# Seaquencer.net
KiCad netlist of a schematic drawn in EAGLE
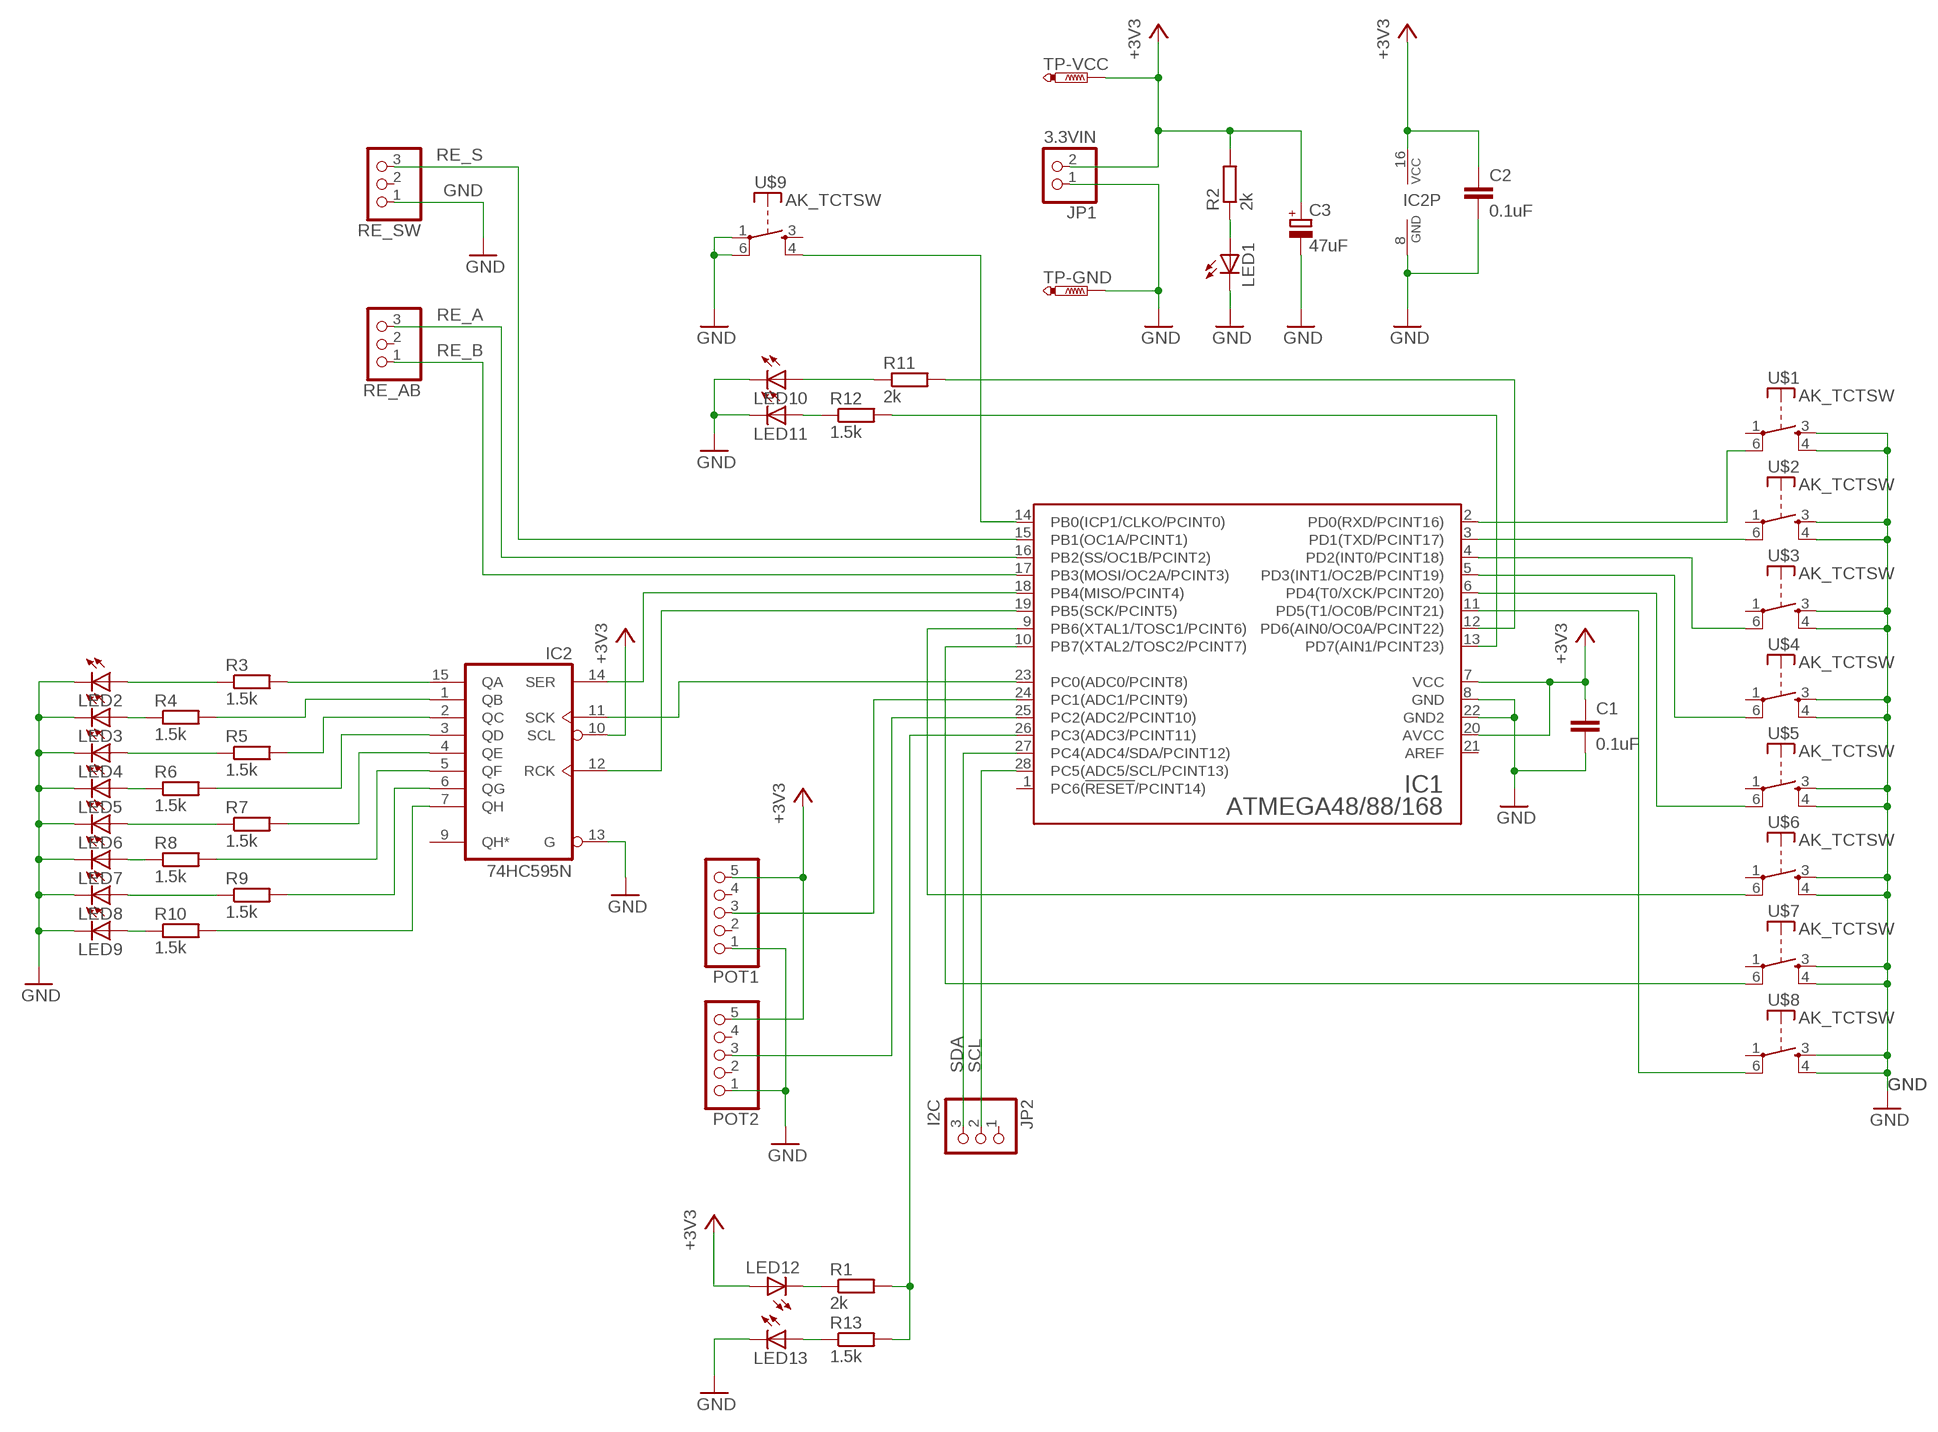
[diagram p0: schematic, sheet 1]

(export (version "E")
  (design (tool "Eeschema 10.0.6"))
  (components
    (comp (ref "C1")
      (value "0.1uF")
      (footprint "eagle-import:C025-024X044")
      (libsource (lib "eagle-import") (part "C-EU025-024X044"))
    )
    (comp (ref "C2")
      (value "0.1uF")
      (footprint "eagle-import:C025-024X044")
      (libsource (lib "eagle-import") (part "C-EU025-024X044"))
    )
    (comp (ref "C3")
      (value "47uF")
      (footprint "eagle-import:E2,5-6")
      (libsource (lib "eagle-import") (part "CPOL-EUE2.5-6"))
    )
    (comp (ref "IC1")
      (value "ATMEGA48/88/168")
      (footprint "eagle-import:DIL28-3")
      (libsource (lib "eagle-import") (part "ATMEGA48/88/168"))
    )
    (comp (ref "IC2")
      (value "74HC595N")
      (footprint "eagle-import:DIL16")
      (libsource (lib "eagle-import") (part "74595NHC"))
    )
    (comp (ref "JP1")
      (value "3.3VIN")
      (footprint "eagle-import:1X02")
      (libsource (lib "eagle-import") (part "PINHD-1X2"))
    )
    (comp (ref "JP2")
      (value "I2C")
      (footprint "eagle-import:1X03")
      (libsource (lib "eagle-import") (part "PINHD-1X3"))
    )
    (comp (ref "LED1")
      (value "LED3MM")
      (footprint "eagle-import:LED3MM")
      (libsource (lib "eagle-import") (part "LED3MM"))
    )
    (comp (ref "LED2")
      (value "LED3MM")
      (footprint "eagle-import:LED3MM")
      (libsource (lib "eagle-import") (part "LED3MM"))
    )
    (comp (ref "LED3")
      (value "LED3MM")
      (footprint "eagle-import:LED3MM")
      (libsource (lib "eagle-import") (part "LED3MM"))
    )
    (comp (ref "LED4")
      (value "LED3MM")
      (footprint "eagle-import:LED3MM")
      (libsource (lib "eagle-import") (part "LED3MM"))
    )
    (comp (ref "LED5")
      (value "LED3MM")
      (footprint "eagle-import:LED3MM")
      (libsource (lib "eagle-import") (part "LED3MM"))
    )
    (comp (ref "LED6")
      (value "LED3MM")
      (footprint "eagle-import:LED3MM")
      (libsource (lib "eagle-import") (part "LED3MM"))
    )
    (comp (ref "LED7")
      (value "LED3MM")
      (footprint "eagle-import:LED3MM")
      (libsource (lib "eagle-import") (part "LED3MM"))
    )
    (comp (ref "LED8")
      (value "LED3MM")
      (footprint "eagle-import:LED3MM")
      (libsource (lib "eagle-import") (part "LED3MM"))
    )
    (comp (ref "LED9")
      (value "LED3MM")
      (footprint "eagle-import:LED3MM")
      (libsource (lib "eagle-import") (part "LED3MM"))
    )
    (comp (ref "LED10")
      (value "LED3MM")
      (footprint "eagle-import:LED3MM")
      (libsource (lib "eagle-import") (part "LED3MM"))
    )
    (comp (ref "LED11")
      (value "LED3MM")
      (footprint "eagle-import:LED3MM")
      (libsource (lib "eagle-import") (part "LED3MM"))
    )
    (comp (ref "LED12")
      (value "LED3MM")
      (footprint "eagle-import:LED3MM")
      (libsource (lib "eagle-import") (part "LED3MM"))
    )
    (comp (ref "LED13")
      (value "LED3MM")
      (footprint "eagle-import:LED3MM")
      (libsource (lib "eagle-import") (part "LED3MM"))
    )
    (comp (ref "POT1")
      (value "PINHD-1X5")
      (footprint "eagle-import:1X05")
      (libsource (lib "eagle-import") (part "PINHD-1X5"))
    )
    (comp (ref "POT2")
      (value "PINHD-1X5")
      (footprint "eagle-import:1X05")
      (libsource (lib "eagle-import") (part "PINHD-1X5"))
    )
    (comp (ref "R1")
      (value "2k")
      (footprint "eagle-import:0207_7")
      (libsource (lib "eagle-import") (part "R-EU_0207/7"))
    )
    (comp (ref "R2")
      (value "2k")
      (footprint "eagle-import:0207_7")
      (libsource (lib "eagle-import") (part "R-EU_0207/7"))
    )
    (comp (ref "R3")
      (value "1.5k")
      (footprint "eagle-import:0207_7")
      (libsource (lib "eagle-import") (part "R-EU_0207/7"))
    )
    (comp (ref "R4")
      (value "1.5k")
      (footprint "eagle-import:0207_7")
      (libsource (lib "eagle-import") (part "R-EU_0207/7"))
    )
    (comp (ref "R5")
      (value "1.5k")
      (footprint "eagle-import:0207_7")
      (libsource (lib "eagle-import") (part "R-EU_0207/7"))
    )
    (comp (ref "R6")
      (value "1.5k")
      (footprint "eagle-import:0207_7")
      (libsource (lib "eagle-import") (part "R-EU_0207/7"))
    )
    (comp (ref "R7")
      (value "1.5k")
      (footprint "eagle-import:0207_7")
      (libsource (lib "eagle-import") (part "R-EU_0207/7"))
    )
    (comp (ref "R8")
      (value "1.5k")
      (footprint "eagle-import:0207_7")
      (libsource (lib "eagle-import") (part "R-EU_0207/7"))
    )
    (comp (ref "R9")
      (value "1.5k")
      (footprint "eagle-import:0207_7")
      (libsource (lib "eagle-import") (part "R-EU_0207/7"))
    )
    (comp (ref "R10")
      (value "1.5k")
      (footprint "eagle-import:0207_7")
      (libsource (lib "eagle-import") (part "R-EU_0207/7"))
    )
    (comp (ref "R11")
      (value "2k")
      (footprint "eagle-import:0207_7")
      (libsource (lib "eagle-import") (part "R-EU_0207/7"))
    )
    (comp (ref "R12")
      (value "1.5k")
      (footprint "eagle-import:0207_7")
      (libsource (lib "eagle-import") (part "R-EU_0207/7"))
    )
    (comp (ref "R13")
      (value "1.5k")
      (footprint "eagle-import:0207_7")
      (libsource (lib "eagle-import") (part "R-EU_0207/7"))
    )
    (comp (ref "RE_AB")
      (value "PINHD-1X3")
      (footprint "eagle-import:1X03")
      (libsource (lib "eagle-import") (part "PINHD-1X3"))
    )
    (comp (ref "RE_SW")
      (value "PINHD-1X3")
      (footprint "eagle-import:1X03")
      (libsource (lib "eagle-import") (part "PINHD-1X3"))
    )
    (comp (ref "TP-GND")
      (value "PTR1PAD1-13")
      (footprint "eagle-import:P1-13")
      (libsource (lib "eagle-import") (part "PTR1PAD1-13"))
    )
    (comp (ref "TP-VCC")
      (value "PTR1PAD1-13")
      (footprint "eagle-import:P1-13")
      (libsource (lib "eagle-import") (part "PTR1PAD1-13"))
    )
    (comp (ref "U$1")
      (value "AK_TCTSW")
      (footprint "eagle-import:TME1")
      (libsource (lib "eagle-import") (part "AK_TCTSW"))
    )
    (comp (ref "U$2")
      (value "AK_TCTSW")
      (footprint "eagle-import:TME1")
      (libsource (lib "eagle-import") (part "AK_TCTSW"))
    )
    (comp (ref "U$3")
      (value "AK_TCTSW")
      (footprint "eagle-import:TME1")
      (libsource (lib "eagle-import") (part "AK_TCTSW"))
    )
    (comp (ref "U$4")
      (value "AK_TCTSW")
      (footprint "eagle-import:TME1")
      (libsource (lib "eagle-import") (part "AK_TCTSW"))
    )
    (comp (ref "U$5")
      (value "AK_TCTSW")
      (footprint "eagle-import:TME1")
      (libsource (lib "eagle-import") (part "AK_TCTSW"))
    )
    (comp (ref "U$6")
      (value "AK_TCTSW")
      (footprint "eagle-import:TME1")
      (libsource (lib "eagle-import") (part "AK_TCTSW"))
    )
    (comp (ref "U$7")
      (value "AK_TCTSW")
      (footprint "eagle-import:TME1")
      (libsource (lib "eagle-import") (part "AK_TCTSW"))
    )
    (comp (ref "U$8")
      (value "AK_TCTSW")
      (footprint "eagle-import:TME1")
      (libsource (lib "eagle-import") (part "AK_TCTSW"))
    )
    (comp (ref "U$9")
      (value "AK_TCTSW")
      (footprint "eagle-import:TME1")
      (libsource (lib "eagle-import") (part "AK_TCTSW"))
    )
  )
  (nets
    (net (code "1") (name "+3V3") (class "Default")
      (node (ref "C1") (pin "1") (pinfunction "1_1") (pintype "passive"))
      (node (ref "C2") (pin "1") (pinfunction "1_1") (pintype "passive"))
      (node (ref "C3") (pin "+") (pinfunction "+_+") (pintype "passive"))
      (node (ref "IC1") (pin "20") (pinfunction "AVCC_20") (pintype "power_in"))
      (node (ref "IC1") (pin "7") (pinfunction "VCC_7") (pintype "power_in"))
      (node (ref "IC2") (pin "10") (pinfunction "SCL_10") (pintype "input"))
      (node (ref "IC2") (pin "16") (pinfunction "VCC_16") (pintype "power_in"))
      (node (ref "JP1") (pin "2") (pinfunction "2_2") (pintype "passive"))
      (node (ref "LED12") (pin "A") (pinfunction "A_A") (pintype "passive"))
      (node (ref "POT1") (pin "5") (pinfunction "5_5") (pintype "passive"))
      (node (ref "POT2") (pin "5") (pinfunction "5_5") (pintype "passive"))
      (node (ref "R2") (pin "2") (pinfunction "2_2") (pintype "passive"))
      (node (ref "TP-VCC") (pin "TP") (pinfunction "TP_TP") (pintype "input"))
    )
    (net (code "2") (name "/RE_A") (class "Default")
      (node (ref "IC1") (pin "16") (pinfunction "PB2(SS/OC1B/PCINT2)_16") (pintype "bidirectional"))
      (node (ref "RE_AB") (pin "3") (pinfunction "3_3") (pintype "passive"))
    )
    (net (code "3") (name "/RE_B") (class "Default")
      (node (ref "IC1") (pin "17") (pinfunction "PB3(MOSI/OC2A/PCINT3)_17") (pintype "bidirectional"))
      (node (ref "RE_AB") (pin "1") (pinfunction "1_1") (pintype "passive"))
    )
    (net (code "4") (name "/RE_S") (class "Default")
      (node (ref "IC1") (pin "15") (pinfunction "PB1(OC1A/PCINT1)_15") (pintype "bidirectional"))
      (node (ref "RE_SW") (pin "3") (pinfunction "3_3") (pintype "passive"))
    )
    (net (code "5") (name "/SCL") (class "Default")
      (node (ref "IC1") (pin "28") (pinfunction "PC5(ADC5/SCL/PCINT13)_28") (pintype "bidirectional"))
      (node (ref "JP2") (pin "2") (pinfunction "2_2") (pintype "passive"))
    )
    (net (code "6") (name "/SDA") (class "Default")
      (node (ref "IC1") (pin "27") (pinfunction "PC4(ADC4/SDA/PCINT12)_27") (pintype "bidirectional"))
      (node (ref "JP2") (pin "3") (pinfunction "3_3") (pintype "passive"))
    )
    (net (code "7") (name "GND") (class "Default")
      (node (ref "C1") (pin "2") (pinfunction "2_2") (pintype "passive"))
      (node (ref "C2") (pin "2") (pinfunction "2_2") (pintype "passive"))
      (node (ref "C3") (pin "-") (pinfunction "-_-") (pintype "passive"))
      (node (ref "IC1") (pin "22") (pinfunction "GND2_22") (pintype "power_in"))
      (node (ref "IC1") (pin "8") (pinfunction "GND_8") (pintype "power_in"))
      (node (ref "IC2") (pin "13") (pinfunction "G_13") (pintype "input"))
      (node (ref "IC2") (pin "8") (pinfunction "GND_8") (pintype "power_in"))
      (node (ref "JP1") (pin "1") (pinfunction "1_1") (pintype "passive"))
      (node (ref "LED1") (pin "K") (pinfunction "C_K") (pintype "passive"))
      (node (ref "LED10") (pin "K") (pinfunction "C_K") (pintype "passive"))
      (node (ref "LED11") (pin "K") (pinfunction "C_K") (pintype "passive"))
      (node (ref "LED13") (pin "K") (pinfunction "C_K") (pintype "passive"))
      (node (ref "LED2") (pin "K") (pinfunction "C_K") (pintype "passive"))
      (node (ref "LED3") (pin "K") (pinfunction "C_K") (pintype "passive"))
      (node (ref "LED4") (pin "K") (pinfunction "C_K") (pintype "passive"))
      (node (ref "LED5") (pin "K") (pinfunction "C_K") (pintype "passive"))
      (node (ref "LED6") (pin "K") (pinfunction "C_K") (pintype "passive"))
      (node (ref "LED7") (pin "K") (pinfunction "C_K") (pintype "passive"))
      (node (ref "LED8") (pin "K") (pinfunction "C_K") (pintype "passive"))
      (node (ref "LED9") (pin "K") (pinfunction "C_K") (pintype "passive"))
      (node (ref "POT1") (pin "1") (pinfunction "1_1") (pintype "passive"))
      (node (ref "POT2") (pin "1") (pinfunction "1_1") (pintype "passive"))
      (node (ref "RE_SW") (pin "1") (pinfunction "1_1") (pintype "passive"))
      (node (ref "TP-GND") (pin "TP") (pinfunction "TP_TP") (pintype "input"))
      (node (ref "U$1") (pin "3") (pinfunction "S_3") (pintype "passive"))
      (node (ref "U$1") (pin "4") (pinfunction "S_4") (pintype "passive"))
      (node (ref "U$2") (pin "3") (pinfunction "S_3") (pintype "passive"))
      (node (ref "U$2") (pin "4") (pinfunction "S_4") (pintype "passive"))
      (node (ref "U$3") (pin "3") (pinfunction "S_3") (pintype "passive"))
      (node (ref "U$3") (pin "4") (pinfunction "S_4") (pintype "passive"))
      (node (ref "U$4") (pin "3") (pinfunction "S_3") (pintype "passive"))
      (node (ref "U$4") (pin "4") (pinfunction "S_4") (pintype "passive"))
      (node (ref "U$5") (pin "3") (pinfunction "S_3") (pintype "passive"))
      (node (ref "U$5") (pin "4") (pinfunction "S_4") (pintype "passive"))
      (node (ref "U$6") (pin "3") (pinfunction "S_3") (pintype "passive"))
      (node (ref "U$6") (pin "4") (pinfunction "S_4") (pintype "passive"))
      (node (ref "U$7") (pin "3") (pinfunction "S_3") (pintype "passive"))
      (node (ref "U$7") (pin "4") (pinfunction "S_4") (pintype "passive"))
      (node (ref "U$8") (pin "3") (pinfunction "S_3") (pintype "passive"))
      (node (ref "U$8") (pin "4") (pinfunction "S_4") (pintype "passive"))
      (node (ref "U$9") (pin "1") (pinfunction "P_1") (pintype "passive"))
      (node (ref "U$9") (pin "6") (pinfunction "P_6") (pintype "passive"))
    )
    (net (code "8") (name "Net-(IC1-PB0(ICP1{slash}CLKO{slash}PCINT0))") (class "Default")
      (node (ref "IC1") (pin "14") (pinfunction "PB0(ICP1/CLKO/PCINT0)_14") (pintype "bidirectional"))
      (node (ref "U$9") (pin "4") (pinfunction "S_4") (pintype "passive"))
    )
    (net (code "9") (name "Net-(IC1-PB4(MISO{slash}PCINT4))") (class "Default")
      (node (ref "IC1") (pin "18") (pinfunction "PB4(MISO/PCINT4)_18") (pintype "bidirectional"))
      (node (ref "IC2") (pin "14") (pinfunction "SER_14") (pintype "input"))
    )
    (net (code "10") (name "Net-(IC1-PB5(SCK{slash}PCINT5))") (class "Default")
      (node (ref "IC1") (pin "19") (pinfunction "PB5(SCK/PCINT5)_19") (pintype "bidirectional"))
      (node (ref "IC2") (pin "12") (pinfunction "RCK_12") (pintype "input"))
    )
    (net (code "11") (name "Net-(IC1-PB6(XTAL1{slash}TOSC1{slash}PCINT6))") (class "Default")
      (node (ref "IC1") (pin "9") (pinfunction "PB6(XTAL1/TOSC1/PCINT6)_9") (pintype "bidirectional"))
      (node (ref "U$6") (pin "6") (pinfunction "P_6") (pintype "passive"))
    )
    (net (code "12") (name "Net-(IC1-PB7(XTAL2{slash}TOSC2{slash}PCINT7))") (class "Default")
      (node (ref "IC1") (pin "10") (pinfunction "PB7(XTAL2/TOSC2/PCINT7)_10") (pintype "bidirectional"))
      (node (ref "U$7") (pin "6") (pinfunction "P_6") (pintype "passive"))
    )
    (net (code "13") (name "Net-(IC1-PC0(ADC0{slash}PCINT8))") (class "Default")
      (node (ref "IC1") (pin "23") (pinfunction "PC0(ADC0/PCINT8)_23") (pintype "bidirectional"))
      (node (ref "IC2") (pin "11") (pinfunction "SCK_11") (pintype "input"))
    )
    (net (code "14") (name "Net-(IC1-PC1(ADC1{slash}PCINT9))") (class "Default")
      (node (ref "IC1") (pin "24") (pinfunction "PC1(ADC1/PCINT9)_24") (pintype "bidirectional"))
      (node (ref "POT1") (pin "3") (pinfunction "3_3") (pintype "passive"))
    )
    (net (code "15") (name "Net-(IC1-PC2(ADC2{slash}PCINT10))") (class "Default")
      (node (ref "IC1") (pin "25") (pinfunction "PC2(ADC2/PCINT10)_25") (pintype "bidirectional"))
      (node (ref "POT2") (pin "3") (pinfunction "3_3") (pintype "passive"))
    )
    (net (code "16") (name "Net-(IC1-PC3(ADC3{slash}PCINT11))") (class "Default")
      (node (ref "IC1") (pin "26") (pinfunction "PC3(ADC3/PCINT11)_26") (pintype "bidirectional"))
      (node (ref "R1") (pin "2") (pinfunction "2_2") (pintype "passive"))
      (node (ref "R13") (pin "2") (pinfunction "2_2") (pintype "passive"))
    )
    (net (code "17") (name "Net-(IC1-PD0(RXD{slash}PCINT16))") (class "Default")
      (node (ref "IC1") (pin "2") (pinfunction "PD0(RXD/PCINT16)_2") (pintype "bidirectional"))
      (node (ref "U$1") (pin "6") (pinfunction "P_6") (pintype "passive"))
    )
    (net (code "18") (name "Net-(IC1-PD1(TXD{slash}PCINT17))") (class "Default")
      (node (ref "IC1") (pin "3") (pinfunction "PD1(TXD/PCINT17)_3") (pintype "bidirectional"))
      (node (ref "U$2") (pin "6") (pinfunction "P_6") (pintype "passive"))
    )
    (net (code "19") (name "Net-(IC1-PD2(INT0{slash}PCINT18))") (class "Default")
      (node (ref "IC1") (pin "4") (pinfunction "PD2(INT0/PCINT18)_4") (pintype "bidirectional"))
      (node (ref "U$3") (pin "6") (pinfunction "P_6") (pintype "passive"))
    )
    (net (code "20") (name "Net-(IC1-PD3(INT1{slash}OC2B{slash}PCINT19))") (class "Default")
      (node (ref "IC1") (pin "5") (pinfunction "PD3(INT1/OC2B/PCINT19)_5") (pintype "bidirectional"))
      (node (ref "U$4") (pin "6") (pinfunction "P_6") (pintype "passive"))
    )
    (net (code "21") (name "Net-(IC1-PD4(T0{slash}XCK{slash}PCINT20))") (class "Default")
      (node (ref "IC1") (pin "6") (pinfunction "PD4(T0/XCK/PCINT20)_6") (pintype "bidirectional"))
      (node (ref "U$5") (pin "6") (pinfunction "P_6") (pintype "passive"))
    )
    (net (code "22") (name "Net-(IC1-PD5(T1{slash}OC0B{slash}PCINT21))") (class "Default")
      (node (ref "IC1") (pin "11") (pinfunction "PD5(T1/OC0B/PCINT21)_11") (pintype "bidirectional"))
      (node (ref "U$8") (pin "6") (pinfunction "P_6") (pintype "passive"))
    )
    (net (code "23") (name "Net-(IC1-PD6(AIN0{slash}OC0A{slash}PCINT22))") (class "Default")
      (node (ref "IC1") (pin "12") (pinfunction "PD6(AIN0/OC0A/PCINT22)_12") (pintype "bidirectional"))
      (node (ref "R11") (pin "2") (pinfunction "2_2") (pintype "passive"))
    )
    (net (code "24") (name "Net-(IC1-PD7(AIN1{slash}PCINT23))") (class "Default")
      (node (ref "IC1") (pin "13") (pinfunction "PD7(AIN1/PCINT23)_13") (pintype "bidirectional"))
      (node (ref "R12") (pin "2") (pinfunction "2_2") (pintype "passive"))
    )
    (net (code "25") (name "Net-(IC2A-QA)") (class "Default")
      (node (ref "IC2") (pin "15") (pinfunction "QA_15") (pintype "tri_state"))
      (node (ref "R3") (pin "2") (pinfunction "2_2") (pintype "passive"))
    )
    (net (code "26") (name "Net-(IC2A-QB)") (class "Default")
      (node (ref "IC2") (pin "1") (pinfunction "QB_1") (pintype "tri_state"))
      (node (ref "R4") (pin "2") (pinfunction "2_2") (pintype "passive"))
    )
    (net (code "27") (name "Net-(IC2A-QC)") (class "Default")
      (node (ref "IC2") (pin "2") (pinfunction "QC_2") (pintype "tri_state"))
      (node (ref "R5") (pin "2") (pinfunction "2_2") (pintype "passive"))
    )
    (net (code "28") (name "Net-(IC2A-QD)") (class "Default")
      (node (ref "IC2") (pin "3") (pinfunction "QD_3") (pintype "tri_state"))
      (node (ref "R6") (pin "2") (pinfunction "2_2") (pintype "passive"))
    )
    (net (code "29") (name "Net-(IC2A-QE)") (class "Default")
      (node (ref "IC2") (pin "4") (pinfunction "QE_4") (pintype "tri_state"))
      (node (ref "R7") (pin "2") (pinfunction "2_2") (pintype "passive"))
    )
    (net (code "30") (name "Net-(IC2A-QF)") (class "Default")
      (node (ref "IC2") (pin "5") (pinfunction "QF_5") (pintype "tri_state"))
      (node (ref "R8") (pin "2") (pinfunction "2_2") (pintype "passive"))
    )
    (net (code "31") (name "Net-(IC2A-QG)") (class "Default")
      (node (ref "IC2") (pin "6") (pinfunction "QG_6") (pintype "tri_state"))
      (node (ref "R9") (pin "2") (pinfunction "2_2") (pintype "passive"))
    )
    (net (code "32") (name "Net-(IC2A-QH)") (class "Default")
      (node (ref "IC2") (pin "7") (pinfunction "QH_7") (pintype "tri_state"))
      (node (ref "R10") (pin "2") (pinfunction "2_2") (pintype "passive"))
    )
    (net (code "33") (name "Net-(LED1-PadA)") (class "Default")
      (node (ref "LED1") (pin "A") (pinfunction "A_A") (pintype "passive"))
      (node (ref "R2") (pin "1") (pinfunction "1_1") (pintype "passive"))
    )
    (net (code "34") (name "Net-(LED2-PadA)") (class "Default")
      (node (ref "LED2") (pin "A") (pinfunction "A_A") (pintype "passive"))
      (node (ref "R3") (pin "1") (pinfunction "1_1") (pintype "passive"))
    )
    (net (code "35") (name "Net-(LED3-PadA)") (class "Default")
      (node (ref "LED3") (pin "A") (pinfunction "A_A") (pintype "passive"))
      (node (ref "R4") (pin "1") (pinfunction "1_1") (pintype "passive"))
    )
    (net (code "36") (name "Net-(LED4-PadA)") (class "Default")
      (node (ref "LED4") (pin "A") (pinfunction "A_A") (pintype "passive"))
      (node (ref "R5") (pin "1") (pinfunction "1_1") (pintype "passive"))
    )
    (net (code "37") (name "Net-(LED5-PadA)") (class "Default")
      (node (ref "LED5") (pin "A") (pinfunction "A_A") (pintype "passive"))
      (node (ref "R6") (pin "1") (pinfunction "1_1") (pintype "passive"))
    )
    (net (code "38") (name "Net-(LED6-PadA)") (class "Default")
      (node (ref "LED6") (pin "A") (pinfunction "A_A") (pintype "passive"))
      (node (ref "R7") (pin "1") (pinfunction "1_1") (pintype "passive"))
    )
    (net (code "39") (name "Net-(LED7-PadA)") (class "Default")
      (node (ref "LED7") (pin "A") (pinfunction "A_A") (pintype "passive"))
      (node (ref "R8") (pin "1") (pinfunction "1_1") (pintype "passive"))
    )
    (net (code "40") (name "Net-(LED8-PadA)") (class "Default")
      (node (ref "LED8") (pin "A") (pinfunction "A_A") (pintype "passive"))
      (node (ref "R9") (pin "1") (pinfunction "1_1") (pintype "passive"))
    )
    (net (code "41") (name "Net-(LED9-PadA)") (class "Default")
      (node (ref "LED9") (pin "A") (pinfunction "A_A") (pintype "passive"))
      (node (ref "R10") (pin "1") (pinfunction "1_1") (pintype "passive"))
    )
    (net (code "42") (name "Net-(LED10-PadA)") (class "Default")
      (node (ref "LED10") (pin "A") (pinfunction "A_A") (pintype "passive"))
      (node (ref "R11") (pin "1") (pinfunction "1_1") (pintype "passive"))
    )
    (net (code "43") (name "Net-(LED11-PadA)") (class "Default")
      (node (ref "LED11") (pin "A") (pinfunction "A_A") (pintype "passive"))
      (node (ref "R12") (pin "1") (pinfunction "1_1") (pintype "passive"))
    )
    (net (code "44") (name "Net-(LED12-C)") (class "Default")
      (node (ref "LED12") (pin "K") (pinfunction "C_K") (pintype "passive"))
      (node (ref "R1") (pin "1") (pinfunction "1_1") (pintype "passive"))
    )
    (net (code "45") (name "Net-(LED13-PadA)") (class "Default")
      (node (ref "LED13") (pin "A") (pinfunction "A_A") (pintype "passive"))
      (node (ref "R13") (pin "1") (pinfunction "1_1") (pintype "passive"))
    )
    (net (code "46") (name "unconnected-(IC1-AREF-Pad21)") (class "Default")
      (node (ref "IC1") (pin "21") (pinfunction "AREF_21") (pintype "passive"))
    )
    (net (code "47") (name "unconnected-(IC1-PC6(~{RESET}{slash}PCINT14)-Pad1)") (class "Default")
      (node (ref "IC1") (pin "1") (pinfunction "PC6(~{RESET}/PCINT14)_1") (pintype "bidirectional"))
    )
    (net (code "48") (name "unconnected-(IC2A-QH*-Pad9)") (class "Default")
      (node (ref "IC2") (pin "9") (pinfunction "QH*_9") (pintype "tri_state"))
    )
    (net (code "49") (name "unconnected-(JP2-Pad1)") (class "Default")
      (node (ref "JP2") (pin "1") (pinfunction "1_1") (pintype "passive"))
    )
    (net (code "50") (name "unconnected-(POT1-Pad2)") (class "Default")
      (node (ref "POT1") (pin "2") (pinfunction "2_2") (pintype "passive"))
    )
    (net (code "51") (name "unconnected-(POT1-Pad4)") (class "Default")
      (node (ref "POT1") (pin "4") (pinfunction "4_4") (pintype "passive"))
    )
    (net (code "52") (name "unconnected-(POT2-Pad2)") (class "Default")
      (node (ref "POT2") (pin "2") (pinfunction "2_2") (pintype "passive"))
    )
    (net (code "53") (name "unconnected-(POT2-Pad4)") (class "Default")
      (node (ref "POT2") (pin "4") (pinfunction "4_4") (pintype "passive"))
    )
    (net (code "54") (name "unconnected-(RE_AB-Pad2)") (class "Default")
      (node (ref "RE_AB") (pin "2") (pinfunction "2_2") (pintype "passive"))
    )
    (net (code "55") (name "unconnected-(RE_SW-Pad2)") (class "Default")
      (node (ref "RE_SW") (pin "2") (pinfunction "2_2") (pintype "passive"))
    )
    (net (code "56") (name "unconnected-(U$1-P-Pad1)") (class "Default")
      (node (ref "U$1") (pin "1") (pinfunction "P_1") (pintype "passive"))
    )
    (net (code "57") (name "unconnected-(U$2-P-Pad1)") (class "Default")
      (node (ref "U$2") (pin "1") (pinfunction "P_1") (pintype "passive"))
    )
    (net (code "58") (name "unconnected-(U$3-P-Pad1)") (class "Default")
      (node (ref "U$3") (pin "1") (pinfunction "P_1") (pintype "passive"))
    )
    (net (code "59") (name "unconnected-(U$4-P-Pad1)") (class "Default")
      (node (ref "U$4") (pin "1") (pinfunction "P_1") (pintype "passive"))
    )
    (net (code "60") (name "unconnected-(U$5-P-Pad1)") (class "Default")
      (node (ref "U$5") (pin "1") (pinfunction "P_1") (pintype "passive"))
    )
    (net (code "61") (name "unconnected-(U$6-P-Pad1)") (class "Default")
      (node (ref "U$6") (pin "1") (pinfunction "P_1") (pintype "passive"))
    )
    (net (code "62") (name "unconnected-(U$7-P-Pad1)") (class "Default")
      (node (ref "U$7") (pin "1") (pinfunction "P_1") (pintype "passive"))
    )
    (net (code "63") (name "unconnected-(U$8-P-Pad1)") (class "Default")
      (node (ref "U$8") (pin "1") (pinfunction "P_1") (pintype "passive"))
    )
    (net (code "64") (name "unconnected-(U$9-S-Pad3)") (class "Default")
      (node (ref "U$9") (pin "3") (pinfunction "S_3") (pintype "passive"))
    )
  )
)
